# radiosonde_lite.net
KiCad netlist of a schematic drawn in EAGLE
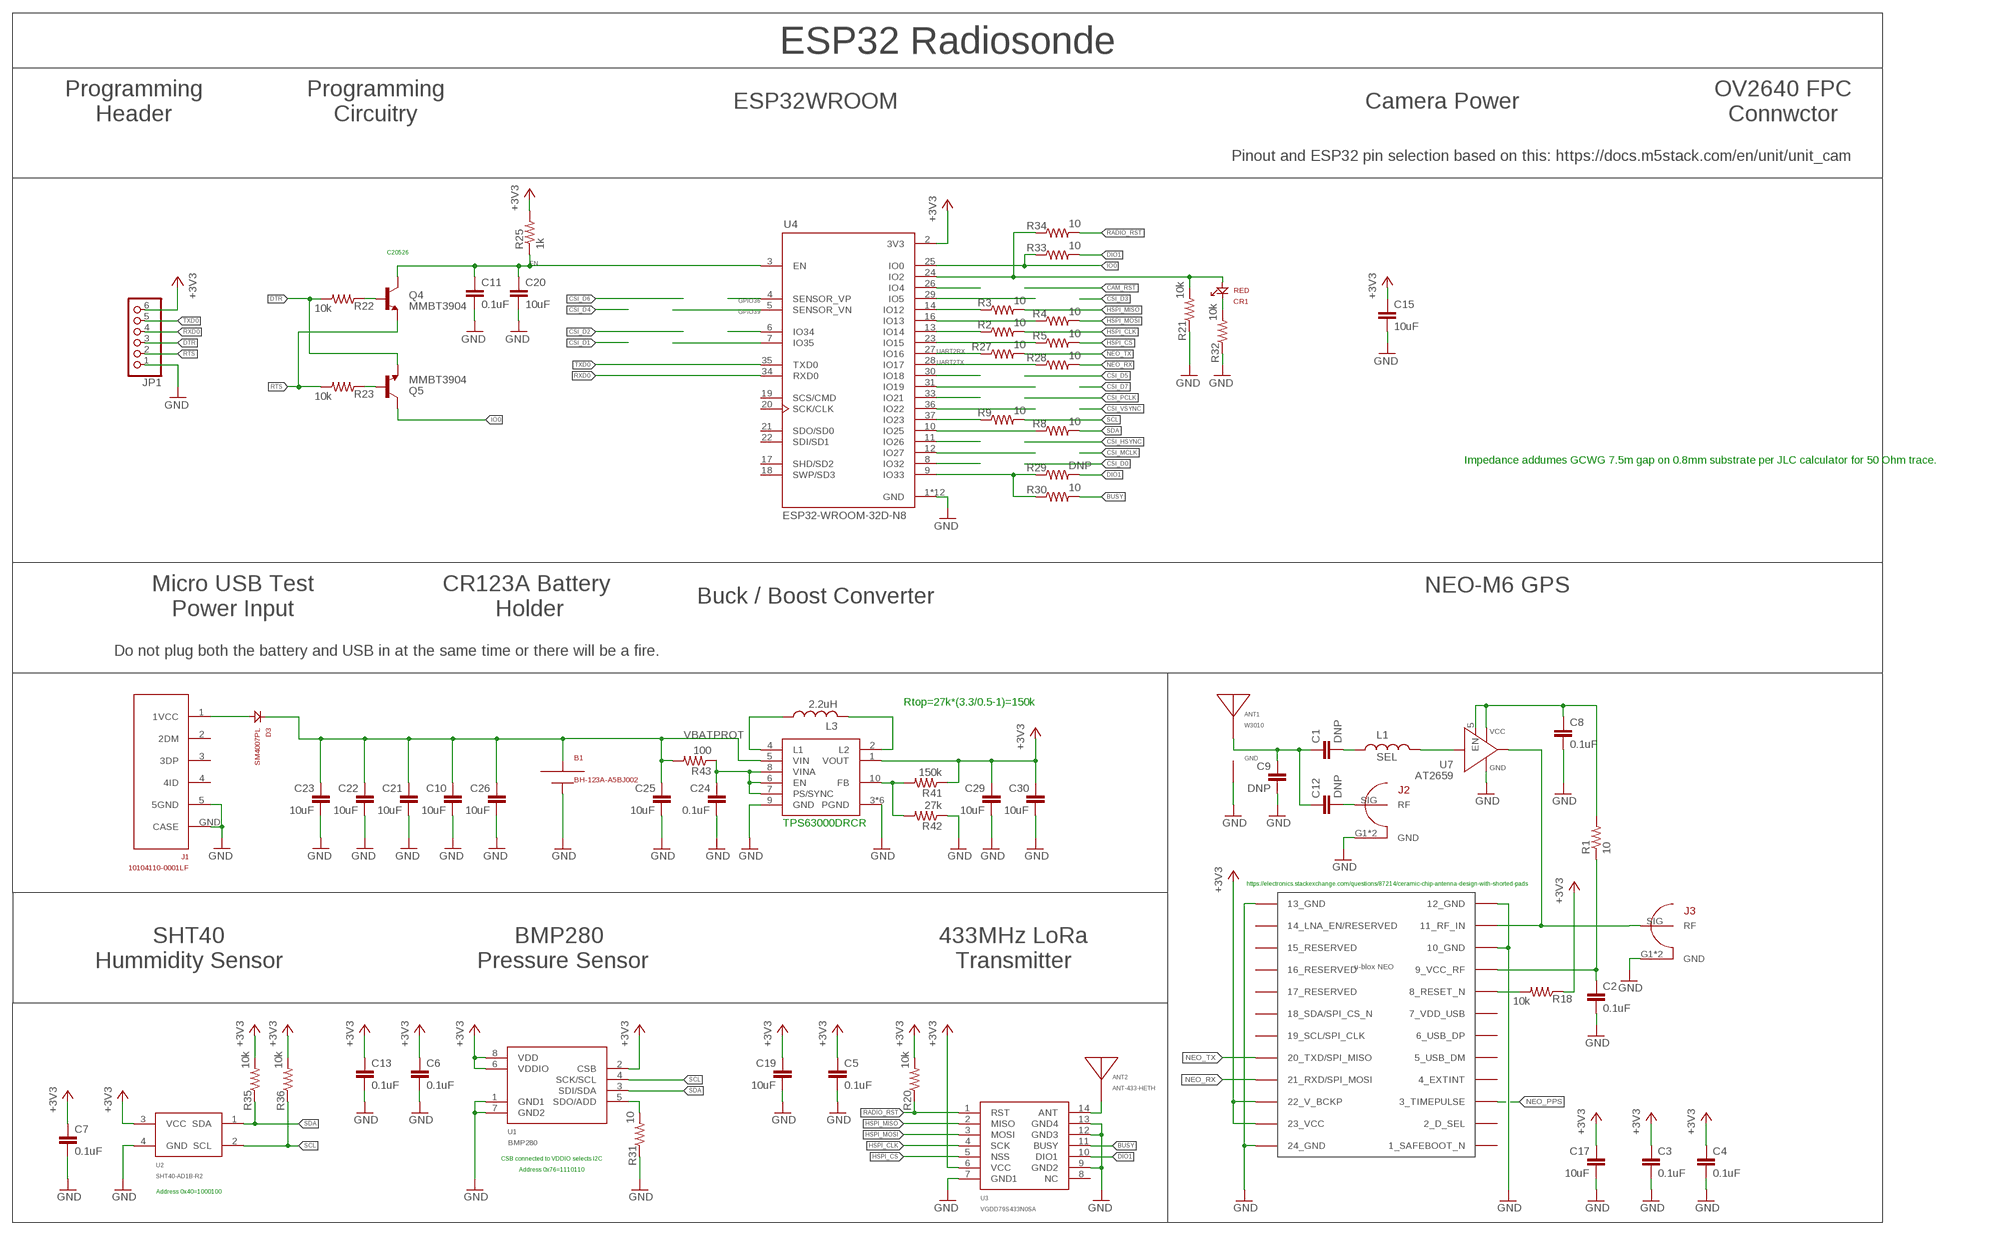
[diagram p0: schematic, sheet 1]

(export (version "E")
  (design (tool "Eeschema 10.0.6"))
  (components
    (comp (ref "ANT1")
      (value "W3010")
      (footprint "eagle-import:W3010")
      (libsource (lib "eagle-import") (part "W3010"))
    )
    (comp (ref "ANT2")
      (value "ANT-433-HETH")
      (footprint "eagle-import:ANT-433-HETH")
      (fields (field (name "PARTNO") "ANT-433-HETH-ND"))
      (libsource (lib "eagle-import") (part "ANT-433-HETH"))
    )
    (comp (ref "B1")
      (value "BH-123A-A5BJ002")
      (footprint "eagle-import:BH-123A-A5BJ002")
      (libsource (lib "eagle-import") (part "BH-123A-A5BJ002"))
    )
    (comp (ref "C1")
      (value "DNP")
      (footprint "eagle-import:0402_INDUCTOR")
      (libsource (lib "eagle-import") (part "0402_CAPACITOR"))
    )
    (comp (ref "C2")
      (value "0.1uF")
      (footprint "eagle-import:0402_INDUCTOR")
      (libsource (lib "eagle-import") (part "0402_CAPACITOR"))
    )
    (comp (ref "C3")
      (value "0.1uF")
      (footprint "eagle-import:0402_INDUCTOR")
      (libsource (lib "eagle-import") (part "0402_CAPACITOR"))
    )
    (comp (ref "C4")
      (value "0.1uF")
      (footprint "eagle-import:0402_INDUCTOR")
      (libsource (lib "eagle-import") (part "0402_CAPACITOR"))
    )
    (comp (ref "C5")
      (value "0.1uF")
      (footprint "eagle-import:0402_INDUCTOR")
      (libsource (lib "eagle-import") (part "0402_CAPACITOR"))
    )
    (comp (ref "C6")
      (value "0.1uF")
      (footprint "eagle-import:0402_INDUCTOR")
      (libsource (lib "eagle-import") (part "0402_CAPACITOR"))
    )
    (comp (ref "C7")
      (value "0.1uF")
      (footprint "eagle-import:0402_INDUCTOR")
      (libsource (lib "eagle-import") (part "0402_CAPACITOR"))
    )
    (comp (ref "C8")
      (value "0.1uF")
      (footprint "eagle-import:0402_INDUCTOR")
      (libsource (lib "eagle-import") (part "0402_CAPACITOR"))
    )
    (comp (ref "C9")
      (value "DNP")
      (footprint "eagle-import:0402_INDUCTOR")
      (libsource (lib "eagle-import") (part "0402_CAPACITOR"))
    )
    (comp (ref "C10")
      (value "10uF")
      (footprint "eagle-import:0603")
      (libsource (lib "eagle-import") (part "0603_CAPACITOR"))
    )
    (comp (ref "C11")
      (value "0.1uF")
      (footprint "eagle-import:0402_INDUCTOR")
      (libsource (lib "eagle-import") (part "0402_CAPACITOR"))
    )
    (comp (ref "C12")
      (value "DNP")
      (footprint "eagle-import:0402_INDUCTOR")
      (libsource (lib "eagle-import") (part "0402_CAPACITOR"))
    )
    (comp (ref "C13")
      (value "0.1uF")
      (footprint "eagle-import:0402_INDUCTOR")
      (libsource (lib "eagle-import") (part "0402_CAPACITOR"))
    )
    (comp (ref "C15")
      (value "10uF")
      (footprint "eagle-import:0603")
      (libsource (lib "eagle-import") (part "0603_CAPACITOR"))
    )
    (comp (ref "C17")
      (value "10uF")
      (footprint "eagle-import:0603")
      (libsource (lib "eagle-import") (part "0603_CAPACITOR"))
    )
    (comp (ref "C19")
      (value "10uF")
      (footprint "eagle-import:0603")
      (libsource (lib "eagle-import") (part "0603_CAPACITOR"))
    )
    (comp (ref "C20")
      (value "10uF")
      (footprint "eagle-import:0603")
      (libsource (lib "eagle-import") (part "0603_CAPACITOR"))
    )
    (comp (ref "C21")
      (value "10uF")
      (footprint "eagle-import:0603")
      (libsource (lib "eagle-import") (part "0603_CAPACITOR"))
    )
    (comp (ref "C22")
      (value "10uF")
      (footprint "eagle-import:0603")
      (libsource (lib "eagle-import") (part "0603_CAPACITOR"))
    )
    (comp (ref "C23")
      (value "10uF")
      (footprint "eagle-import:0603")
      (libsource (lib "eagle-import") (part "0603_CAPACITOR"))
    )
    (comp (ref "C24")
      (value "0.1uF")
      (footprint "eagle-import:0603")
      (libsource (lib "eagle-import") (part "0603_CAPACITOR"))
    )
    (comp (ref "C25")
      (value "10uF")
      (footprint "eagle-import:0603")
      (libsource (lib "eagle-import") (part "0603_CAPACITOR"))
    )
    (comp (ref "C26")
      (value "10uF")
      (footprint "eagle-import:0603")
      (libsource (lib "eagle-import") (part "0603_CAPACITOR"))
    )
    (comp (ref "C29")
      (value "10uF")
      (footprint "eagle-import:0603")
      (libsource (lib "eagle-import") (part "0603_CAPACITOR"))
    )
    (comp (ref "C30")
      (value "10uF")
      (footprint "eagle-import:0603")
      (libsource (lib "eagle-import") (part "0603_CAPACITOR"))
    )
    (comp (ref "CR1")
      (value "RED")
      (footprint "eagle-import:0603_DIODE")
      (fields (field (name "PARTNO") "732-4978-1-ND"))
      (libsource (lib "eagle-import") (part "150060RS75000"))
    )
    (comp (ref "D3")
      (value "SM4007PL")
      (footprint "eagle-import:SOD123(AK)")
      (libsource (lib "eagle-import") (part "SM4007PL"))
    )
    (comp (ref "IC1")
      (value "NEO-M8")
      (footprint "eagle-import:NEO-M8")
      (libsource (lib "eagle-import") (part "NEO-M8"))
    )
    (comp (ref "J1")
      (value "10104110-0001LF")
      (footprint "eagle-import:MICRO_USB")
      (fields (field (name "PARTNO") "609-4052-1-ND"))
      (libsource (lib "eagle-import") (part "10104110-0001LF"))
    )
    (comp (ref "J2")
      (value "CONUFL001-SMD")
      (footprint "eagle-import:U.FL")
      (libsource (lib "eagle-import") (part "CONUFL001-SMD"))
    )
    (comp (ref "J3")
      (value "CONUFL001-SMD")
      (footprint "eagle-import:U.FL")
      (libsource (lib "eagle-import") (part "CONUFL001-SMD"))
    )
    (comp (ref "JP1")
      (value "PINHD-1X6")
      (footprint "eagle-import:1X06")
      (libsource (lib "eagle-import") (part "PINHD-1X6"))
    )
    (comp (ref "L1")
      (value "SEL")
      (footprint "eagle-import:0402_INDUCTOR")
      (libsource (lib "eagle-import") (part "0402_INDUCTOR"))
    )
    (comp (ref "L3")
      (value "2.2uH")
      (footprint "eagle-import:CY43")
      (libsource (lib "eagle-import") (part "CY43-2.2UH"))
    )
    (comp (ref "Q4")
      (value "MMBT3904")
      (footprint "eagle-import:SOT23-3_CENTERED")
      (libsource (lib "eagle-import") (part "MMBT3904-TPCENTERED"))
    )
    (comp (ref "Q5")
      (value "MMBT3904")
      (footprint "eagle-import:SOT23-3_CENTERED")
      (libsource (lib "eagle-import") (part "MMBT3904-TPCENTERED"))
    )
    (comp (ref "R1")
      (value "10")
      (footprint "eagle-import:R0402")
      (libsource (lib "eagle-import") (part "0402_RESISTOR"))
    )
    (comp (ref "R2")
      (value "10")
      (footprint "eagle-import:R0402")
      (libsource (lib "eagle-import") (part "0402_RESISTOR"))
    )
    (comp (ref "R3")
      (value "10")
      (footprint "eagle-import:R0402")
      (libsource (lib "eagle-import") (part "0402_RESISTOR"))
    )
    (comp (ref "R4")
      (value "10")
      (footprint "eagle-import:R0402")
      (libsource (lib "eagle-import") (part "0402_RESISTOR"))
    )
    (comp (ref "R5")
      (value "10")
      (footprint "eagle-import:R0402")
      (libsource (lib "eagle-import") (part "0402_RESISTOR"))
    )
    (comp (ref "R8")
      (value "10")
      (footprint "eagle-import:R0402")
      (libsource (lib "eagle-import") (part "0402_RESISTOR"))
    )
    (comp (ref "R9")
      (value "10")
      (footprint "eagle-import:R0402")
      (libsource (lib "eagle-import") (part "0402_RESISTOR"))
    )
    (comp (ref "R18")
      (value "10k")
      (footprint "eagle-import:R0402")
      (libsource (lib "eagle-import") (part "0402_RESISTOR"))
    )
    (comp (ref "R20")
      (value "10k")
      (footprint "eagle-import:R0402")
      (libsource (lib "eagle-import") (part "0402_RESISTOR"))
    )
    (comp (ref "R21")
      (value "10k")
      (footprint "eagle-import:R0402")
      (libsource (lib "eagle-import") (part "0402_RESISTOR"))
    )
    (comp (ref "R22")
      (value "10k")
      (footprint "eagle-import:R0402")
      (libsource (lib "eagle-import") (part "0402_RESISTOR"))
    )
    (comp (ref "R23")
      (value "10k")
      (footprint "eagle-import:R0402")
      (libsource (lib "eagle-import") (part "0402_RESISTOR"))
    )
    (comp (ref "R25")
      (value "1k")
      (footprint "eagle-import:0603")
      (libsource (lib "eagle-import") (part "0603_RESISTOR"))
    )
    (comp (ref "R27")
      (value "10")
      (footprint "eagle-import:R0402")
      (libsource (lib "eagle-import") (part "0402_RESISTOR"))
    )
    (comp (ref "R28")
      (value "10")
      (footprint "eagle-import:R0402")
      (libsource (lib "eagle-import") (part "0402_RESISTOR"))
    )
    (comp (ref "R29")
      (value "DNP")
      (footprint "eagle-import:R0402")
      (libsource (lib "eagle-import") (part "0402_RESISTOR"))
    )
    (comp (ref "R30")
      (value "10")
      (footprint "eagle-import:R0402")
      (libsource (lib "eagle-import") (part "0402_RESISTOR"))
    )
    (comp (ref "R31")
      (value "10")
      (footprint "eagle-import:R0402")
      (libsource (lib "eagle-import") (part "0402_RESISTOR"))
    )
    (comp (ref "R32")
      (value "10k")
      (footprint "eagle-import:R0402")
      (libsource (lib "eagle-import") (part "0402_RESISTOR"))
    )
    (comp (ref "R33")
      (value "10")
      (footprint "eagle-import:R0402")
      (libsource (lib "eagle-import") (part "0402_RESISTOR"))
    )
    (comp (ref "R34")
      (value "10")
      (footprint "eagle-import:R0402")
      (libsource (lib "eagle-import") (part "0402_RESISTOR"))
    )
    (comp (ref "R35")
      (value "10k")
      (footprint "eagle-import:R0402")
      (libsource (lib "eagle-import") (part "0402_RESISTOR"))
    )
    (comp (ref "R36")
      (value "10k")
      (footprint "eagle-import:R0402")
      (libsource (lib "eagle-import") (part "0402_RESISTOR"))
    )
    (comp (ref "R41")
      (value "150k")
      (footprint "eagle-import:0603")
      (libsource (lib "eagle-import") (part "0603_RESISTOR"))
    )
    (comp (ref "R42")
      (value "27k")
      (footprint "eagle-import:0603")
      (libsource (lib "eagle-import") (part "0603_RESISTOR"))
    )
    (comp (ref "R43")
      (value "100")
      (footprint "eagle-import:0603")
      (libsource (lib "eagle-import") (part "0603_RESISTOR"))
    )
    (comp (ref "U1")
      (value "BMP280")
      (footprint "eagle-import:BME280")
      (fields (field (name "PARTNO") "828-1064-1-ND"))
      (libsource (lib "eagle-import") (part "BMP280"))
    )
    (comp (ref "U2")
      (value "SHT40-AD1B-R2")
      (footprint "eagle-import:SHT40")
      (libsource (lib "eagle-import") (part "SHT40-AD1B-R2"))
    )
    (comp (ref "U3")
      (value "VGDD79S433N0SA")
      (footprint "eagle-import:VGDD79S433N0SA")
      (libsource (lib "eagle-import") (part "VGDD79S433N0SA"))
    )
    (comp (ref "U4")
      (value "ESP32-WROOM-32D-N8")
      (footprint "eagle-import:MODULE_ESP32-WROOM-32D")
      (fields (field (name "MF") "Espressif Systems") (field (name "MP") "ESP32-WROOM-32D"))
      (libsource (lib "eagle-import") (part "ESP32-WROOM-32D"))
    )
    (comp (ref "U6")
      (value "TPS63000DRCR")
      (footprint "eagle-import:S-PVSON-N10")
      (fields (field (name "PARTNO") "296-19641-1-ND"))
      (libsource (lib "eagle-import") (part "TPS63000DRCR"))
    )
    (comp (ref "U7")
      (value "AT2659")
      (footprint "eagle-import:6DFN-1X1.6")
      (libsource (lib "eagle-import") (part "AT2659"))
    )
  )
  (nets
    (net (code "1") (name "+3V3") (class "Default")
      (node (ref "C13") (pin "P$1") (pinfunction "1_P$1") (pintype "passive"))
      (node (ref "C15") (pin "1") (pinfunction "1_1") (pintype "passive"))
      (node (ref "C17") (pin "1") (pinfunction "1_1") (pintype "passive"))
      (node (ref "C19") (pin "1") (pinfunction "1_1") (pintype "passive"))
      (node (ref "C29") (pin "1") (pinfunction "1_1") (pintype "passive"))
      (node (ref "C3") (pin "P$1") (pinfunction "1_P$1") (pintype "passive"))
      (node (ref "C30") (pin "1") (pinfunction "1_1") (pintype "passive"))
      (node (ref "C4") (pin "P$1") (pinfunction "1_P$1") (pintype "passive"))
      (node (ref "C5") (pin "P$1") (pinfunction "1_P$1") (pintype "passive"))
      (node (ref "C6") (pin "P$1") (pinfunction "1_P$1") (pintype "passive"))
      (node (ref "C7") (pin "P$1") (pinfunction "1_P$1") (pintype "passive"))
      (node (ref "IC1") (pin "22") (pinfunction "22_V_BCKP_22") (pintype "bidirectional"))
      (node (ref "IC1") (pin "23") (pinfunction "23_VCC_23") (pintype "bidirectional"))
      (node (ref "JP1") (pin "6") (pinfunction "6_6") (pintype "passive"))
      (node (ref "R18") (pin "1") (pinfunction "1_1") (pintype "passive"))
      (node (ref "R20") (pin "2") (pinfunction "2_2") (pintype "passive"))
      (node (ref "R25") (pin "2") (pinfunction "2_2") (pintype "passive"))
      (node (ref "R35") (pin "2") (pinfunction "2_2") (pintype "passive"))
      (node (ref "R36") (pin "2") (pinfunction "2_2") (pintype "passive"))
      (node (ref "R41") (pin "1") (pinfunction "1_1") (pintype "passive"))
      (node (ref "U1") (pin "2") (pinfunction "CSB_2") (pintype "bidirectional"))
      (node (ref "U1") (pin "6") (pinfunction "VDDIO_6") (pintype "bidirectional"))
      (node (ref "U1") (pin "8") (pinfunction "VDD_8") (pintype "bidirectional"))
      (node (ref "U2") (pin "3") (pinfunction "VCC_3") (pintype "bidirectional"))
      (node (ref "U3") (pin "6") (pinfunction "VCC_6") (pintype "bidirectional"))
      (node (ref "U4") (pin "2") (pinfunction "3V3_2") (pintype "power_in"))
      (node (ref "U6") (pin "1") (pinfunction "VOUT_1") (pintype "bidirectional"))
    )
    (net (code "2") (name "/EN") (class "Default")
      (node (ref "C11") (pin "P$1") (pinfunction "1_P$1") (pintype "passive"))
      (node (ref "C20") (pin "1") (pinfunction "1_1") (pintype "passive"))
      (node (ref "Q4") (pin "3") (pinfunction "C_3") (pintype "passive"))
      (node (ref "R25") (pin "1") (pinfunction "1_1") (pintype "passive"))
      (node (ref "U4") (pin "3") (pinfunction "EN_3") (pintype "input"))
    )
    (net (code "3") (name "/GPIO36") (class "Default")
      (node (ref "U4") (pin "4") (pinfunction "SENSOR_VP_4") (pintype "input"))
    )
    (net (code "4") (name "/GPIO39") (class "Default")
      (node (ref "U4") (pin "5") (pinfunction "SENSOR_VN_5") (pintype "input"))
    )
    (net (code "5") (name "/UART2RX") (class "Default")
      (node (ref "R27") (pin "1") (pinfunction "1_1") (pintype "passive"))
      (node (ref "U4") (pin "27") (pinfunction "IO16_27") (pintype "bidirectional"))
    )
    (net (code "6") (name "/UART2TX") (class "Default")
      (node (ref "R28") (pin "1") (pinfunction "1_1") (pintype "passive"))
      (node (ref "U4") (pin "28") (pinfunction "IO17_28") (pintype "bidirectional"))
    )
    (net (code "7") (name "/VBATPROT") (class "Default")
      (node (ref "B1") (pin "P") (pinfunction "+_P") (pintype "bidirectional"))
      (node (ref "C10") (pin "1") (pinfunction "1_1") (pintype "passive"))
      (node (ref "C21") (pin "1") (pinfunction "1_1") (pintype "passive"))
      (node (ref "C22") (pin "1") (pinfunction "1_1") (pintype "passive"))
      (node (ref "C23") (pin "1") (pinfunction "1_1") (pintype "passive"))
      (node (ref "C25") (pin "1") (pinfunction "1_1") (pintype "passive"))
      (node (ref "C26") (pin "1") (pinfunction "1_1") (pintype "passive"))
      (node (ref "D3") (pin "K") (pinfunction "K_K") (pintype "bidirectional"))
      (node (ref "R43") (pin "2") (pinfunction "2_2") (pintype "passive"))
      (node (ref "U6") (pin "5") (pinfunction "VIN_5") (pintype "bidirectional"))
    )
    (net (code "8") (name "BUSY") (class "Default")
      (node (ref "R30") (pin "2") (pinfunction "2_2") (pintype "passive"))
      (node (ref "U3") (pin "11") (pinfunction "BUSY_11") (pintype "bidirectional"))
    )
    (net (code "22") (name "DIO1") (class "Default")
      (node (ref "R29") (pin "2") (pinfunction "2_2") (pintype "passive"))
      (node (ref "R33") (pin "2") (pinfunction "2_2") (pintype "passive"))
      (node (ref "U3") (pin "10") (pinfunction "DIO1_10") (pintype "bidirectional"))
    )
    (net (code "23") (name "DTR") (class "Default")
      (node (ref "JP1") (pin "3") (pinfunction "3_3") (pintype "passive"))
      (node (ref "Q5") (pin "2") (pinfunction "E_2") (pintype "passive"))
      (node (ref "R22") (pin "2") (pinfunction "2_2") (pintype "passive"))
    )
    (net (code "24") (name "GND") (class "Default")
      (node (ref "ANT1") (pin "P$1") (pinfunction "GND_P$1") (pintype "bidirectional"))
      (node (ref "ANT1") (pin "P$3") (pinfunction "GND_P$3") (pintype "bidirectional"))
      (node (ref "B1") (pin "N") (pinfunction "-_N") (pintype "bidirectional"))
      (node (ref "C10") (pin "2") (pinfunction "2_2") (pintype "passive"))
      (node (ref "C11") (pin "P$2") (pinfunction "2_P$2") (pintype "passive"))
      (node (ref "C13") (pin "P$2") (pinfunction "2_P$2") (pintype "passive"))
      (node (ref "C15") (pin "2") (pinfunction "2_2") (pintype "passive"))
      (node (ref "C17") (pin "2") (pinfunction "2_2") (pintype "passive"))
      (node (ref "C19") (pin "2") (pinfunction "2_2") (pintype "passive"))
      (node (ref "C2") (pin "P$2") (pinfunction "2_P$2") (pintype "passive"))
      (node (ref "C20") (pin "2") (pinfunction "2_2") (pintype "passive"))
      (node (ref "C21") (pin "2") (pinfunction "2_2") (pintype "passive"))
      (node (ref "C22") (pin "2") (pinfunction "2_2") (pintype "passive"))
      (node (ref "C23") (pin "2") (pinfunction "2_2") (pintype "passive"))
      (node (ref "C24") (pin "2") (pinfunction "2_2") (pintype "passive"))
      (node (ref "C25") (pin "2") (pinfunction "2_2") (pintype "passive"))
      (node (ref "C26") (pin "2") (pinfunction "2_2") (pintype "passive"))
      (node (ref "C29") (pin "2") (pinfunction "2_2") (pintype "passive"))
      (node (ref "C3") (pin "P$2") (pinfunction "2_P$2") (pintype "passive"))
      (node (ref "C30") (pin "2") (pinfunction "2_2") (pintype "passive"))
      (node (ref "C4") (pin "P$2") (pinfunction "2_P$2") (pintype "passive"))
      (node (ref "C5") (pin "P$2") (pinfunction "2_P$2") (pintype "passive"))
      (node (ref "C6") (pin "P$2") (pinfunction "2_P$2") (pintype "passive"))
      (node (ref "C7") (pin "P$2") (pinfunction "2_P$2") (pintype "passive"))
      (node (ref "C8") (pin "P$2") (pinfunction "2_P$2") (pintype "passive"))
      (node (ref "C9") (pin "P$2") (pinfunction "2_P$2") (pintype "passive"))
      (node (ref "IC1") (pin "10") (pinfunction "10_GND_10") (pintype "bidirectional"))
      (node (ref "IC1") (pin "12") (pinfunction "12_GND_12") (pintype "bidirectional"))
      (node (ref "IC1") (pin "13") (pinfunction "13_GND_13") (pintype "bidirectional"))
      (node (ref "IC1") (pin "24") (pinfunction "24_GND_24") (pintype "bidirectional"))
      (node (ref "J1") (pin "5") (pinfunction "5GND_5") (pintype "bidirectional"))
      (node (ref "J1") (pin "GND") (pinfunction "CASE_GND") (pintype "bidirectional"))
      (node (ref "J2") (pin "G1") (pinfunction "GND_G1") (pintype "bidirectional"))
      (node (ref "J2") (pin "G2") (pinfunction "GND_G2") (pintype "bidirectional"))
      (node (ref "J3") (pin "G1") (pinfunction "GND_G1") (pintype "bidirectional"))
      (node (ref "J3") (pin "G2") (pinfunction "GND_G2") (pintype "bidirectional"))
      (node (ref "JP1") (pin "1") (pinfunction "1_1") (pintype "passive"))
      (node (ref "R21") (pin "1") (pinfunction "1_1") (pintype "passive"))
      (node (ref "R31") (pin "1") (pinfunction "1_1") (pintype "passive"))
      (node (ref "R32") (pin "1") (pinfunction "1_1") (pintype "passive"))
      (node (ref "R42") (pin "1") (pinfunction "1_1") (pintype "passive"))
      (node (ref "U1") (pin "1") (pinfunction "GND1_1") (pintype "bidirectional"))
      (node (ref "U1") (pin "7") (pinfunction "GND2_7") (pintype "bidirectional"))
      (node (ref "U2") (pin "4") (pinfunction "GND_4") (pintype "bidirectional"))
      (node (ref "U3") (pin "12") (pinfunction "GND3_12") (pintype "bidirectional"))
      (node (ref "U3") (pin "13") (pinfunction "GND4_13") (pintype "bidirectional"))
      (node (ref "U3") (pin "7") (pinfunction "GND1_7") (pintype "bidirectional"))
      (node (ref "U3") (pin "9") (pinfunction "GND2_9") (pintype "bidirectional"))
      (node (ref "U4") (pin "1") (pinfunction "GND_1") (pintype "power_in"))
      (node (ref "U4") (pin "15") (pinfunction "GND_15") (pintype "power_in"))
      (node (ref "U4") (pin "38") (pinfunction "GND_38") (pintype "power_in"))
      (node (ref "U4") (pin "39_1") (pinfunction "GND_39_1") (pintype "power_in"))
      (node (ref "U4") (pin "39_2") (pinfunction "GND_39_2") (pintype "power_in"))
      (node (ref "U4") (pin "39_3") (pinfunction "GND_39_3") (pintype "power_in"))
      (node (ref "U4") (pin "39_4") (pinfunction "GND_39_4") (pintype "power_in"))
      (node (ref "U4") (pin "39_5") (pinfunction "GND_39_5") (pintype "power_in"))
      (node (ref "U4") (pin "39_6") (pinfunction "GND_39_6") (pintype "power_in"))
      (node (ref "U4") (pin "39_7") (pinfunction "GND_39_7") (pintype "power_in"))
      (node (ref "U4") (pin "39_8") (pinfunction "GND_39_8") (pintype "power_in"))
      (node (ref "U4") (pin "39_9") (pinfunction "GND_39_9") (pintype "power_in"))
      (node (ref "U6") (pin "3") (pinfunction "PGND_3") (pintype "bidirectional"))
      (node (ref "U6") (pin "9") (pinfunction "GND_9") (pintype "bidirectional"))
      (node (ref "U6") (pin "PG") (pinfunction "PGND_PG") (pintype "bidirectional"))
      (node (ref "U6") (pin "PG1") (pinfunction "PGND_PG1") (pintype "bidirectional"))
      (node (ref "U6") (pin "PG2") (pinfunction "PGND_PG2") (pintype "bidirectional"))
      (node (ref "U6") (pin "PG3") (pinfunction "PGND_PG3") (pintype "bidirectional"))
      (node (ref "U6") (pin "PG4") (pinfunction "PGND_PG4") (pintype "bidirectional"))
      (node (ref "U7") (pin "1") (pinfunction "GND_1") (pintype "bidirectional"))
      (node (ref "U7") (pin "2") (pinfunction "GND_2") (pintype "bidirectional"))
    )
    (net (code "25") (name "HSPI_CLK") (class "Default")
      (node (ref "R2") (pin "2") (pinfunction "2_2") (pintype "passive"))
      (node (ref "U3") (pin "4") (pinfunction "SCK_4") (pintype "bidirectional"))
    )
    (net (code "26") (name "HSPI_CS") (class "Default")
      (node (ref "R5") (pin "2") (pinfunction "2_2") (pintype "passive"))
      (node (ref "U3") (pin "5") (pinfunction "NSS_5") (pintype "bidirectional"))
    )
    (net (code "27") (name "HSPI_MISO") (class "Default")
      (node (ref "R3") (pin "2") (pinfunction "2_2") (pintype "passive"))
      (node (ref "U3") (pin "2") (pinfunction "MISO_2") (pintype "bidirectional"))
    )
    (net (code "28") (name "HSPI_MOSI") (class "Default")
      (node (ref "R4") (pin "2") (pinfunction "2_2") (pintype "passive"))
      (node (ref "U3") (pin "3") (pinfunction "MOSI_3") (pintype "bidirectional"))
    )
    (net (code "29") (name "IO0") (class "Default")
      (node (ref "Q5") (pin "3") (pinfunction "C_3") (pintype "passive"))
      (node (ref "R33") (pin "1") (pinfunction "1_1") (pintype "passive"))
      (node (ref "U4") (pin "25") (pinfunction "IO0_25") (pintype "bidirectional"))
    )
    (net (code "30") (name "NEO_PPS") (class "Default")
      (node (ref "IC1") (pin "3") (pinfunction "3_TIMEPULSE_3") (pintype "bidirectional"))
    )
    (net (code "31") (name "NEO_RX") (class "Default")
      (node (ref "IC1") (pin "21") (pinfunction "21_RXD/SPI_MOSI_21") (pintype "bidirectional"))
      (node (ref "R28") (pin "2") (pinfunction "2_2") (pintype "passive"))
    )
    (net (code "32") (name "NEO_TX") (class "Default")
      (node (ref "IC1") (pin "20") (pinfunction "20_TXD/SPI_MISO_20") (pintype "bidirectional"))
      (node (ref "R27") (pin "2") (pinfunction "2_2") (pintype "passive"))
    )
    (net (code "33") (name "Net-(ANT1-ANT)") (class "Default")
      (node (ref "ANT1") (pin "P$2") (pinfunction "ANT_P$2") (pintype "bidirectional"))
      (node (ref "C1") (pin "P$1") (pinfunction "1_P$1") (pintype "passive"))
      (node (ref "C12") (pin "P$1") (pinfunction "1_P$1") (pintype "passive"))
      (node (ref "C9") (pin "P$1") (pinfunction "1_P$1") (pintype "passive"))
    )
    (net (code "34") (name "Net-(C1-2)") (class "Default")
      (node (ref "C1") (pin "P$2") (pinfunction "2_P$2") (pintype "passive"))
      (node (ref "L1") (pin "P$1") (pinfunction "P$1_P$1") (pintype "bidirectional"))
    )
    (net (code "35") (name "Net-(C2-1)") (class "Default")
      (node (ref "C2") (pin "P$1") (pinfunction "1_P$1") (pintype "passive"))
      (node (ref "IC1") (pin "9") (pinfunction "9_VCC_RF_9") (pintype "bidirectional"))
      (node (ref "R1") (pin "1") (pinfunction "1_1") (pintype "passive"))
    )
    (net (code "36") (name "Net-(C8-1)") (class "Default")
      (node (ref "C8") (pin "P$1") (pinfunction "1_P$1") (pintype "passive"))
      (node (ref "R1") (pin "2") (pinfunction "2_2") (pintype "passive"))
      (node (ref "U7") (pin "4") (pinfunction "VS_4") (pintype "bidirectional"))
      (node (ref "U7") (pin "5") (pinfunction "EN_5") (pintype "bidirectional"))
    )
    (net (code "37") (name "Net-(C12-2)") (class "Default")
      (node (ref "C12") (pin "P$2") (pinfunction "2_P$2") (pintype "passive"))
      (node (ref "J2") (pin "SIG") (pinfunction "RF_SIG") (pintype "bidirectional"))
    )
    (net (code "38") (name "Net-(CR1-PadK)") (class "Default")
      (node (ref "CR1") (pin "K") (pinfunction "K_K") (pintype "bidirectional"))
      (node (ref "R32") (pin "2") (pinfunction "2_2") (pintype "passive"))
    )
    (net (code "39") (name "Net-(IC1-8_RESET_N)") (class "Default")
      (node (ref "IC1") (pin "8") (pinfunction "8_RESET_N_8") (pintype "bidirectional"))
      (node (ref "R18") (pin "2") (pinfunction "2_2") (pintype "passive"))
    )
    (net (code "40") (name "Net-(IC1-11_RF_IN)") (class "Default")
      (node (ref "IC1") (pin "11") (pinfunction "11_RF_IN_11") (pintype "bidirectional"))
      (node (ref "J3") (pin "SIG") (pinfunction "RF_SIG") (pintype "bidirectional"))
      (node (ref "U7") (pin "6") (pinfunction "RF_OUT_6") (pintype "bidirectional"))
    )
    (net (code "41") (name "Net-(J1-1VCC)") (class "Default")
      (node (ref "D3") (pin "A") (pinfunction "A_A") (pintype "bidirectional"))
      (node (ref "J1") (pin "1") (pinfunction "1VCC_1") (pintype "bidirectional"))
    )
    (net (code "42") (name "Net-(L3-1)") (class "Default")
      (node (ref "L3") (pin "P$1") (pinfunction "1_P$1") (pintype "passive"))
      (node (ref "U6") (pin "4") (pinfunction "L1_4") (pintype "bidirectional"))
    )
    (net (code "43") (name "Net-(L3-2)") (class "Default")
      (node (ref "L3") (pin "P$2") (pinfunction "2_P$2") (pintype "passive"))
      (node (ref "U6") (pin "2") (pinfunction "L2_2") (pintype "bidirectional"))
    )
    (net (code "44") (name "Net-(Q4-B)") (class "Default")
      (node (ref "Q4") (pin "1") (pinfunction "B_1") (pintype "passive"))
      (node (ref "R22") (pin "1") (pinfunction "1_1") (pintype "passive"))
    )
    (net (code "45") (name "Net-(Q5-B)") (class "Default")
      (node (ref "Q5") (pin "1") (pinfunction "B_1") (pintype "passive"))
      (node (ref "R23") (pin "1") (pinfunction "1_1") (pintype "passive"))
    )
    (net (code "46") (name "Net-(U1-SDO{slash}ADD)") (class "Default")
      (node (ref "R31") (pin "2") (pinfunction "2_2") (pintype "passive"))
      (node (ref "U1") (pin "5") (pinfunction "SDO/ADD_5") (pintype "bidirectional"))
    )
    (net (code "47") (name "Net-(U3-ANT)") (class "Default")
      (node (ref "ANT2") (pin "IN1") (pinfunction "P$1_IN1") (pintype "bidirectional"))
      (node (ref "ANT2") (pin "IN2") (pinfunction "P$1_IN2") (pintype "bidirectional"))
      (node (ref "U3") (pin "14") (pinfunction "ANT_14") (pintype "bidirectional"))
    )
    (net (code "48") (name "Net-(U4-IO2)") (class "Default")
      (node (ref "CR1") (pin "A") (pinfunction "A_A") (pintype "bidirectional"))
      (node (ref "R21") (pin "2") (pinfunction "2_2") (pintype "passive"))
      (node (ref "R34") (pin "1") (pinfunction "1_1") (pintype "passive"))
      (node (ref "U4") (pin "24") (pinfunction "IO2_24") (pintype "bidirectional"))
    )
    (net (code "49") (name "Net-(U4-IO12)") (class "Default")
      (node (ref "R3") (pin "1") (pinfunction "1_1") (pintype "passive"))
      (node (ref "U4") (pin "14") (pinfunction "IO12_14") (pintype "bidirectional"))
    )
    (net (code "50") (name "Net-(U4-IO13)") (class "Default")
      (node (ref "R4") (pin "1") (pinfunction "1_1") (pintype "passive"))
      (node (ref "U4") (pin "16") (pinfunction "IO13_16") (pintype "bidirectional"))
    )
    (net (code "51") (name "Net-(U4-IO14)") (class "Default")
      (node (ref "R2") (pin "1") (pinfunction "1_1") (pintype "passive"))
      (node (ref "U4") (pin "13") (pinfunction "IO14_13") (pintype "bidirectional"))
    )
    (net (code "52") (name "Net-(U4-IO15)") (class "Default")
      (node (ref "R5") (pin "1") (pinfunction "1_1") (pintype "passive"))
      (node (ref "U4") (pin "23") (pinfunction "IO15_23") (pintype "bidirectional"))
    )
    (net (code "53") (name "Net-(U4-IO23)") (class "Default")
      (node (ref "R9") (pin "1") (pinfunction "1_1") (pintype "passive"))
      (node (ref "U4") (pin "37") (pinfunction "IO23_37") (pintype "bidirectional"))
    )
    (net (code "54") (name "Net-(U4-IO25)") (class "Default")
      (node (ref "R8") (pin "1") (pinfunction "1_1") (pintype "passive"))
      (node (ref "U4") (pin "10") (pinfunction "IO25_10") (pintype "bidirectional"))
    )
    (net (code "55") (name "Net-(U4-IO33)") (class "Default")
      (node (ref "R29") (pin "1") (pinfunction "1_1") (pintype "passive"))
      (node (ref "R30") (pin "1") (pinfunction "1_1") (pintype "passive"))
      (node (ref "U4") (pin "9") (pinfunction "IO33_9") (pintype "bidirectional"))
    )
    (net (code "56") (name "Net-(U6-EN)") (class "Default")
      (node (ref "C24") (pin "1") (pinfunction "1_1") (pintype "passive"))
      (node (ref "R43") (pin "1") (pinfunction "1_1") (pintype "passive"))
      (node (ref "U6") (pin "6") (pinfunction "EN_6") (pintype "bidirectional"))
      (node (ref "U6") (pin "7") (pinfunction "PS/SYNC_7") (pintype "bidirectional"))
      (node (ref "U6") (pin "8") (pinfunction "VINA_8") (pintype "bidirectional"))
    )
    (net (code "57") (name "Net-(U6-FB)") (class "Default")
      (node (ref "R41") (pin "2") (pinfunction "2_2") (pintype "passive"))
      (node (ref "R42") (pin "2") (pinfunction "2_2") (pintype "passive"))
      (node (ref "U6") (pin "10") (pinfunction "FB_10") (pintype "bidirectional"))
    )
    (net (code "58") (name "Net-(U7-RF_IN)") (class "Default")
      (node (ref "L1") (pin "P$2") (pinfunction "P$2_P$2") (pintype "bidirectional"))
      (node (ref "U7") (pin "3") (pinfunction "RF_IN_3") (pintype "bidirectional"))
    )
    (net (code "59") (name "RADIO_RST") (class "Default")
      (node (ref "R20") (pin "1") (pinfunction "1_1") (pintype "passive"))
      (node (ref "R34") (pin "2") (pinfunction "2_2") (pintype "passive"))
      (node (ref "U3") (pin "1") (pinfunction "RST_1") (pintype "bidirectional"))
    )
    (net (code "60") (name "RTS") (class "Default")
      (node (ref "JP1") (pin "2") (pinfunction "2_2") (pintype "passive"))
      (node (ref "Q4") (pin "2") (pinfunction "E_2") (pintype "passive"))
      (node (ref "R23") (pin "2") (pinfunction "2_2") (pintype "passive"))
    )
    (net (code "61") (name "RXD0") (class "Default")
      (node (ref "JP1") (pin "4") (pinfunction "4_4") (pintype "passive"))
      (node (ref "U4") (pin "34") (pinfunction "RXD0_34") (pintype "bidirectional"))
    )
    (net (code "62") (name "SCL") (class "Default")
      (node (ref "R36") (pin "1") (pinfunction "1_1") (pintype "passive"))
      (node (ref "R9") (pin "2") (pinfunction "2_2") (pintype "passive"))
      (node (ref "U1") (pin "4") (pinfunction "SCK/SCL_4") (pintype "bidirectional"))
      (node (ref "U2") (pin "2") (pinfunction "SCL_2") (pintype "bidirectional"))
    )
    (net (code "63") (name "SDA") (class "Default")
      (node (ref "R35") (pin "1") (pinfunction "1_1") (pintype "passive"))
      (node (ref "R8") (pin "2") (pinfunction "2_2") (pintype "passive"))
      (node (ref "U1") (pin "3") (pinfunction "SDI/SDA_3") (pintype "bidirectional"))
      (node (ref "U2") (pin "1") (pinfunction "SDA_1") (pintype "bidirectional"))
    )
    (net (code "64") (name "TXD0") (class "Default")
      (node (ref "JP1") (pin "5") (pinfunction "5_5") (pintype "passive"))
      (node (ref "U4") (pin "35") (pinfunction "TXD0_35") (pintype "bidirectional"))
    )
    (net (code "65") (name "unconnected-(IC1-1_SAFEBOOT_N-Pad1)") (class "Default")
      (node (ref "IC1") (pin "1") (pinfunction "1_SAFEBOOT_N_1") (pintype "bidirectional"))
    )
    (net (code "66") (name "unconnected-(IC1-2_D_SEL-Pad2)") (class "Default")
      (node (ref "IC1") (pin "2") (pinfunction "2_D_SEL_2") (pintype "bidirectional"))
    )
    (net (code "67") (name "unconnected-(IC1-4_EXTINT-Pad4)") (class "Default")
      (node (ref "IC1") (pin "4") (pinfunction "4_EXTINT_4") (pintype "bidirectional"))
    )
    (net (code "68") (name "unconnected-(IC1-5_USB_DM-Pad5)") (class "Default")
      (node (ref "IC1") (pin "5") (pinfunction "5_USB_DM_5") (pintype "bidirectional"))
    )
    (net (code "69") (name "unconnected-(IC1-6_USB_DP-Pad6)") (class "Default")
      (node (ref "IC1") (pin "6") (pinfunction "6_USB_DP_6") (pintype "bidirectional"))
    )
    (net (code "70") (name "unconnected-(IC1-7_VDD_USB-Pad7)") (class "Default")
      (node (ref "IC1") (pin "7") (pinfunction "7_VDD_USB_7") (pintype "bidirectional"))
    )
    (net (code "71") (name "unconnected-(IC1-14_LNA_EN{slash}RESERVED-Pad14)") (class "Default")
      (node (ref "IC1") (pin "14") (pinfunction "14_LNA_EN/RESERVED_14") (pintype "bidirectional"))
    )
    (net (code "72") (name "unconnected-(IC1-15_RESERVED-Pad15)") (class "Default")
      (node (ref "IC1") (pin "15") (pinfunction "15_RESERVED_15") (pintype "bidirectional"))
    )
    (net (code "73") (name "unconnected-(IC1-16_RESERVED-Pad16)") (class "Default")
      (node (ref "IC1") (pin "16") (pinfunction "16_RESERVED_16") (pintype "bidirectional"))
    )
    (net (code "74") (name "unconnected-(IC1-17_RESERVED-Pad17)") (class "Default")
      (node (ref "IC1") (pin "17") (pinfunction "17_RESERVED_17") (pintype "bidirectional"))
    )
    (net (code "75") (name "unconnected-(IC1-18_SDA{slash}SPI_CS_N-Pad18)") (class "Default")
      (node (ref "IC1") (pin "18") (pinfunction "18_SDA/SPI_CS_N_18") (pintype "bidirectional"))
    )
    (net (code "76") (name "unconnected-(IC1-19_SCL{slash}SPI_CLK-Pad19)") (class "Default")
      (node (ref "IC1") (pin "19") (pinfunction "19_SCL/SPI_CLK_19") (pintype "bidirectional"))
    )
    (net (code "77") (name "unconnected-(J1-2DM-Pad2)") (class "Default")
      (node (ref "J1") (pin "2") (pinfunction "2DM_2") (pintype "bidirectional"))
    )
    (net (code "78") (name "unconnected-(J1-3DP-Pad3)") (class "Default")
      (node (ref "J1") (pin "3") (pinfunction "3DP_3") (pintype "bidirectional"))
    )
    (net (code "79") (name "unconnected-(J1-4ID-Pad4)") (class "Default")
      (node (ref "J1") (pin "4") (pinfunction "4ID_4") (pintype "bidirectional"))
    )
    (net (code "80") (name "unconnected-(U3-NC-Pad8)") (class "Default")
      (node (ref "U3") (pin "8") (pinfunction "NC_8") (pintype "bidirectional"))
    )
    (net (code "81") (name "unconnected-(U4-IO4-Pad26)") (class "Default")
      (node (ref "U4") (pin "26") (pinfunction "IO4_26") (pintype "bidirectional"))
    )
    (net (code "82") (name "unconnected-(U4-IO5-Pad29)") (class "Default")
      (node (ref "U4") (pin "29") (pinfunction "IO5_29") (pintype "bidirectional"))
    )
    (net (code "83") (name "unconnected-(U4-IO18-Pad30)") (class "Default")
      (node (ref "U4") (pin "30") (pinfunction "IO18_30") (pintype "bidirectional"))
    )
    (net (code "84") (name "unconnected-(U4-IO19-Pad31)") (class "Default")
      (node (ref "U4") (pin "31") (pinfunction "IO19_31") (pintype "bidirectional"))
    )
    (net (code "85") (name "unconnected-(U4-IO21-Pad33)") (class "Default")
      (node (ref "U4") (pin "33") (pinfunction "IO21_33") (pintype "bidirectional"))
    )
    (net (code "86") (name "unconnected-(U4-IO22-Pad36)") (class "Default")
      (node (ref "U4") (pin "36") (pinfunction "IO22_36") (pintype "bidirectional"))
    )
    (net (code "87") (name "unconnected-(U4-IO26-Pad11)") (class "Default")
      (node (ref "U4") (pin "11") (pinfunction "IO26_11") (pintype "bidirectional"))
    )
    (net (code "88") (name "unconnected-(U4-IO27-Pad12)") (class "Default")
      (node (ref "U4") (pin "12") (pinfunction "IO27_12") (pintype "bidirectional"))
    )
    (net (code "89") (name "unconnected-(U4-IO32-Pad8)") (class "Default")
      (node (ref "U4") (pin "8") (pinfunction "IO32_8") (pintype "bidirectional"))
    )
    (net (code "90") (name "unconnected-(U4-IO34-Pad6)") (class "Default")
      (node (ref "U4") (pin "6") (pinfunction "IO34_6") (pintype "input"))
    )
    (net (code "91") (name "unconnected-(U4-IO35-Pad7)") (class "Default")
      (node (ref "U4") (pin "7") (pinfunction "IO35_7") (pintype "input"))
    )
    (net (code "92") (name "unconnected-(U4-SCK{slash}CLK-Pad20)") (class "Default")
      (node (ref "U4") (pin "20") (pinfunction "SCK/CLK_20") (pintype "bidirectional"))
    )
    (net (code "93") (name "unconnected-(U4-SCS{slash}CMD-Pad19)") (class "Default")
      (node (ref "U4") (pin "19") (pinfunction "SCS/CMD_19") (pintype "bidirectional"))
    )
    (net (code "94") (name "unconnected-(U4-SDI{slash}SD1-Pad22)") (class "Default")
      (node (ref "U4") (pin "22") (pinfunction "SDI/SD1_22") (pintype "bidirectional"))
    )
    (net (code "95") (name "unconnected-(U4-SDO{slash}SD0-Pad21)") (class "Default")
      (node (ref "U4") (pin "21") (pinfunction "SDO/SD0_21") (pintype "bidirectional"))
    )
    (net (code "96") (name "unconnected-(U4-SHD{slash}SD2-Pad17)") (class "Default")
      (node (ref "U4") (pin "17") (pinfunction "SHD/SD2_17") (pintype "bidirectional"))
    )
    (net (code "97") (name "unconnected-(U4-SWP{slash}SD3-Pad18)") (class "Default")
      (node (ref "U4") (pin "18") (pinfunction "SWP/SD3_18") (pintype "bidirectional"))
    )
  )
)
